# 07_-_Leds_-_OptoCoupler_Input.net
KiCad netlist of a schematic drawn in Altium Designer
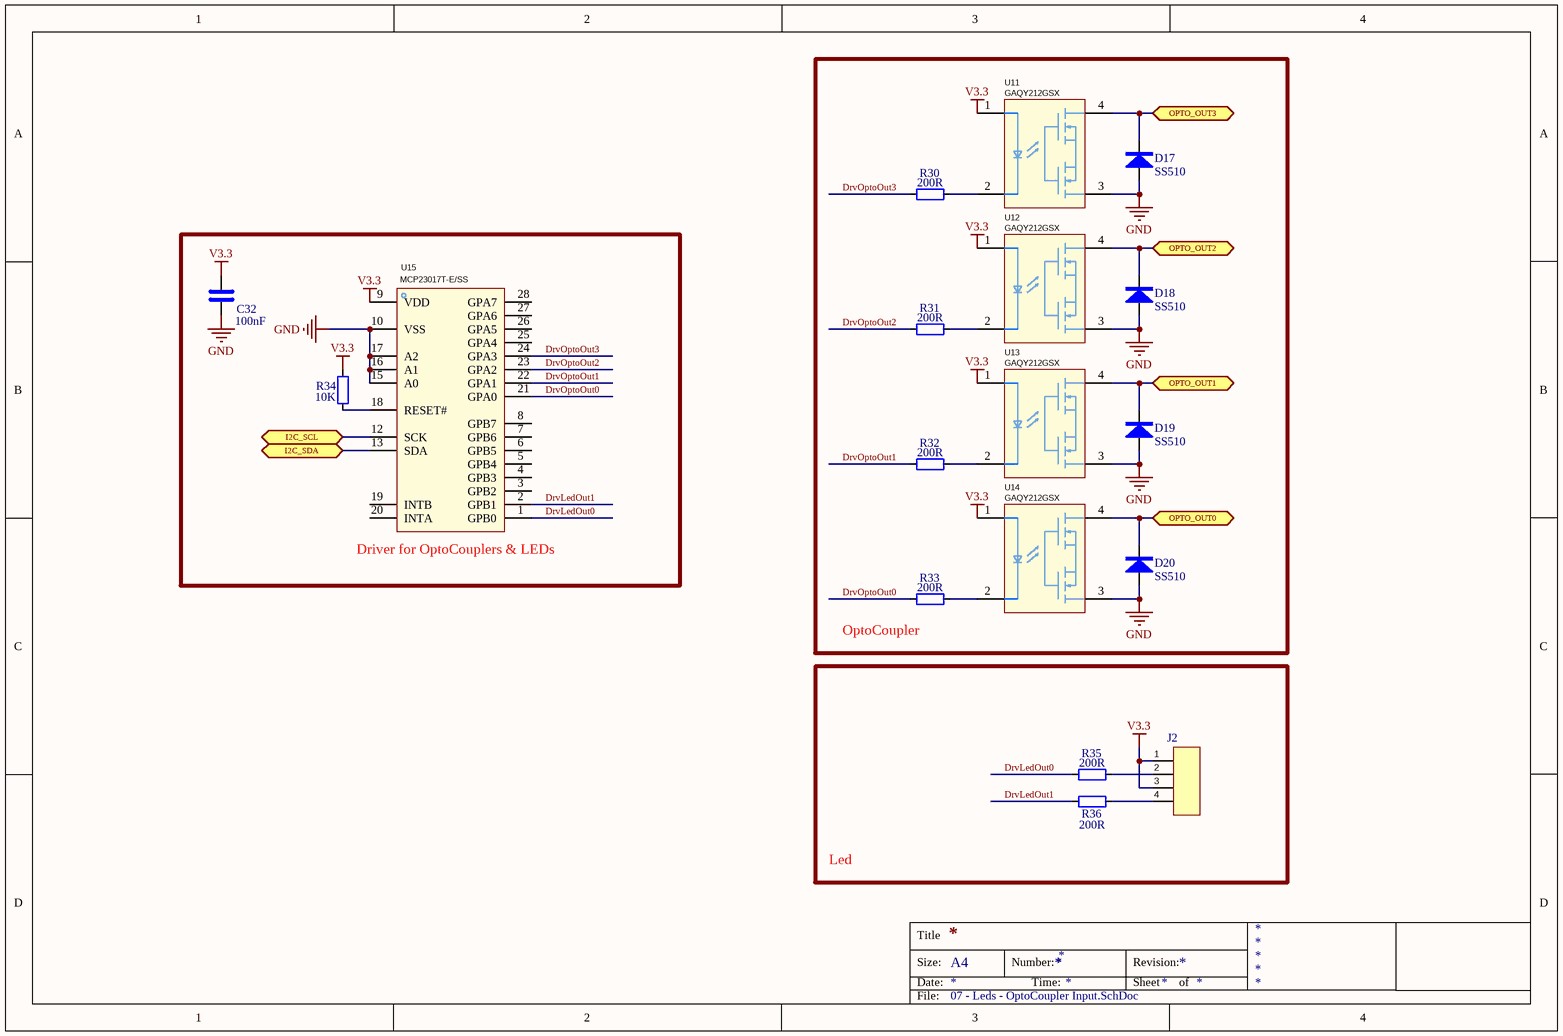
[diagram p0: 07 - Leds - OptoCoupler Input.SchDoc]

(export (version "E")
  (design (tool "Eeschema 10.0.6"))
  (components
    (comp (ref "C32")
      (value "100nF")
      (footprint "CAP_0603")
      (fields (field (name "LCSC PART") "C6119867"))
      (libsource (lib "WalterFeels") (part "C"))
    )
    (comp (ref "D17")
      (value "SS510")
      (footprint "S1M-13-F")
      (fields (field (name "LCSC PART") "C65010") (field (name "Comment") "DIODE SCHOTTKY 100V 5A DO214AC"))
      (libsource (lib "MIKRODEV_LIBRARY_v2") (part "DIODE SCHOTTKY 100V 5A DO214AC"))
    )
    (comp (ref "D18")
      (value "SS510")
      (footprint "S1M-13-F")
      (fields (field (name "LCSC PART") "C65010") (field (name "Comment") "DIODE SCHOTTKY 100V 5A DO214AC"))
      (libsource (lib "MIKRODEV_LIBRARY_v2") (part "DIODE SCHOTTKY 100V 5A DO214AC"))
    )
    (comp (ref "D19")
      (value "SS510")
      (footprint "S1M-13-F")
      (fields (field (name "LCSC PART") "C65010") (field (name "Comment") "DIODE SCHOTTKY 100V 5A DO214AC"))
      (libsource (lib "MIKRODEV_LIBRARY_v2") (part "DIODE SCHOTTKY 100V 5A DO214AC"))
    )
    (comp (ref "D20")
      (value "SS510")
      (footprint "S1M-13-F")
      (fields (field (name "LCSC PART") "C65010") (field (name "Comment") "DIODE SCHOTTKY 100V 5A DO214AC"))
      (libsource (lib "MIKRODEV_LIBRARY_v2") (part "DIODE SCHOTTKY 100V 5A DO214AC"))
    )
    (comp (ref "J2")
      (value "Conn_01x04_Male")
      (footprint "PinHeader_1x04_P2.54mm_Vertical")
      (description "4P 2.54mm Single Row 1x4P Plugin,P=2.54mm Pin Headers ROHS")
      (fields (field (name "LCSC PART") "C5116483"))
      (libsource (lib "WalterFeels") (part "Conn_01x04_Male"))
    )
    (comp (ref "R30")
      (value "200R")
      (footprint "RES_0603")
      (fields (field (name "LCSC PART") "C2907123") (field (name "Comment") "200R %5"))
      (libsource (lib "Device") (part "R"))
    )
    (comp (ref "R31")
      (value "200R")
      (footprint "RES_0603")
      (fields (field (name "LCSC PART") "C2907123") (field (name "Comment") "200R %5"))
      (libsource (lib "Device") (part "R"))
    )
    (comp (ref "R32")
      (value "200R")
      (footprint "RES_0603")
      (fields (field (name "LCSC PART") "C2907123") (field (name "Comment") "200R %5"))
      (libsource (lib "Device") (part "R"))
    )
    (comp (ref "R33")
      (value "200R")
      (footprint "RES_0603")
      (fields (field (name "LCSC PART") "C2907123") (field (name "Comment") "200R %5"))
      (libsource (lib "Device") (part "R"))
    )
    (comp (ref "R34")
      (value "10K")
      (footprint "RES_0603")
      (fields (field (name "LCSC PART") "C25804") (field (name "Comment") "10K 1%"))
      (libsource (lib "") (part "R_1"))
    )
    (comp (ref "R35")
      (value "200R")
      (footprint "RES_0603")
      (fields (field (name "LCSC PART") "C2907123") (field (name "Comment") "200R %5"))
      (libsource (lib "Device") (part "R"))
    )
    (comp (ref "R36")
      (value "200R")
      (footprint "RES_0603")
      (fields (field (name "LCSC PART") "C2907123") (field (name "Comment") "200R %5"))
      (libsource (lib "Device") (part "R"))
    )
    (comp (ref "U11")
      (value "GAQY212GSX")
      (footprint "SOP-4_L4.3-W4.4-P2.54-LS6.8-TR")
      (description "1.32V 60V 180mΩ 1A SOP-4 Solid State Relays (MOS Output) ROHS")
      (fields (field (name "MANUFACTURER") "SUPSiC(国晶微半导体)") (field (name "LCSC PART") "C19271988"))
      (libsource (lib "WalterFeels") (part "GAQY212GSX"))
    )
    (comp (ref "U12")
      (value "GAQY212GSX")
      (footprint "SOP-4_L4.3-W4.4-P2.54-LS6.8-TR")
      (description "1.32V 60V 180mΩ 1A SOP-4 Solid State Relays (MOS Output) ROHS")
      (fields (field (name "MANUFACTURER") "SUPSiC(国晶微半导体)") (field (name "LCSC PART") "C19271988"))
      (libsource (lib "WalterFeels") (part "GAQY212GSX"))
    )
    (comp (ref "U13")
      (value "GAQY212GSX")
      (footprint "SOP-4_L4.3-W4.4-P2.54-LS6.8-TR")
      (description "1.32V 60V 180mΩ 1A SOP-4 Solid State Relays (MOS Output) ROHS")
      (fields (field (name "MANUFACTURER") "SUPSiC(国晶微半导体)") (field (name "LCSC PART") "C19271988"))
      (libsource (lib "WalterFeels") (part "GAQY212GSX"))
    )
    (comp (ref "U14")
      (value "GAQY212GSX")
      (footprint "SOP-4_L4.3-W4.4-P2.54-LS6.8-TR")
      (description "1.32V 60V 180mΩ 1A SOP-4 Solid State Relays (MOS Output) ROHS")
      (fields (field (name "MANUFACTURER") "SUPSiC(国晶微半导体)") (field (name "LCSC PART") "C19271988"))
      (libsource (lib "WalterFeels") (part "GAQY212GSX"))
    )
    (comp (ref "U15")
      (value "MCP23017T-E/SS")
      (footprint "SSOP-28_L10.2-W5.3-P0.65-LS7.8-BL")
      (description "16-Bit I/O Expander with Serial Interface")
      (fields (field (name "MANUFACTURER") "MICROCHIP(美国微芯)") (field (name "LCSC PART") "C558584"))
      (libsource (lib "WalterFeels") (part "MCP23017T-E/SS"))
    )
  )
  (nets
    (net (code "1") (name "/DrvLedOut0") (class "Default")
      (node (ref "R35") (pin "1") (pinfunction "1_1") (pintype "passive"))
      (node (ref "U15") (pin "1") (pinfunction "GPB0_1") (pintype "passive"))
    )
    (net (code "2") (name "/DrvLedOut1") (class "Default")
      (node (ref "R36") (pin "1") (pinfunction "1_1") (pintype "passive"))
      (node (ref "U15") (pin "2") (pinfunction "GPB1_2") (pintype "passive"))
    )
    (net (code "3") (name "/DrvOptoOut0") (class "Default")
      (node (ref "R33") (pin "1") (pinfunction "1_1") (pintype "passive"))
      (node (ref "U15") (pin "21") (pinfunction "GPA0_21") (pintype "passive"))
    )
    (net (code "4") (name "/DrvOptoOut1") (class "Default")
      (node (ref "R32") (pin "1") (pinfunction "1_1") (pintype "passive"))
      (node (ref "U15") (pin "22") (pinfunction "GPA1_22") (pintype "passive"))
    )
    (net (code "5") (name "/DrvOptoOut2") (class "Default")
      (node (ref "R31") (pin "1") (pinfunction "1_1") (pintype "passive"))
      (node (ref "U15") (pin "23") (pinfunction "GPA2_23") (pintype "passive"))
    )
    (net (code "6") (name "/DrvOptoOut3") (class "Default")
      (node (ref "R30") (pin "1") (pinfunction "1_1") (pintype "passive"))
      (node (ref "U15") (pin "24") (pinfunction "GPA3_24") (pintype "passive"))
    )
    (net (code "7") (name "/I2C_SCL") (class "Default")
      (node (ref "U15") (pin "12") (pinfunction "SCK_12") (pintype "passive"))
    )
    (net (code "8") (name "/I2C_SDA") (class "Default")
      (node (ref "U15") (pin "13") (pinfunction "SDA_13") (pintype "passive"))
    )
    (net (code "9") (name "/OPTO_OUT0") (class "Default")
      (node (ref "D20") (pin "1") (pinfunction "K_1") (pintype "passive"))
      (node (ref "U14") (pin "4") (pinfunction "4_4") (pintype "passive"))
    )
    (net (code "10") (name "/OPTO_OUT1") (class "Default")
      (node (ref "D19") (pin "1") (pinfunction "K_1") (pintype "passive"))
      (node (ref "U13") (pin "4") (pinfunction "4_4") (pintype "passive"))
    )
    (net (code "11") (name "/OPTO_OUT2") (class "Default")
      (node (ref "D18") (pin "1") (pinfunction "K_1") (pintype "passive"))
      (node (ref "U12") (pin "4") (pinfunction "4_4") (pintype "passive"))
    )
    (net (code "12") (name "/OPTO_OUT3") (class "Default")
      (node (ref "D17") (pin "1") (pinfunction "K_1") (pintype "passive"))
      (node (ref "U11") (pin "4") (pinfunction "4_4") (pintype "passive"))
    )
    (net (code "13") (name "GND") (class "Default")
      (node (ref "C32") (pin "2") (pinfunction "2_2") (pintype "passive"))
      (node (ref "D17") (pin "2") (pinfunction "A_2") (pintype "passive"))
      (node (ref "D18") (pin "2") (pinfunction "A_2") (pintype "passive"))
      (node (ref "D19") (pin "2") (pinfunction "A_2") (pintype "passive"))
      (node (ref "D20") (pin "2") (pinfunction "A_2") (pintype "passive"))
      (node (ref "U11") (pin "3") (pinfunction "3_3") (pintype "passive"))
      (node (ref "U12") (pin "3") (pinfunction "3_3") (pintype "passive"))
      (node (ref "U13") (pin "3") (pinfunction "3_3") (pintype "passive"))
      (node (ref "U14") (pin "3") (pinfunction "3_3") (pintype "passive"))
      (node (ref "U15") (pin "10") (pinfunction "VSS_10") (pintype "passive"))
      (node (ref "U15") (pin "15") (pinfunction "A0_15") (pintype "passive"))
      (node (ref "U15") (pin "16") (pinfunction "A1_16") (pintype "passive"))
      (node (ref "U15") (pin "17") (pinfunction "A2_17") (pintype "passive"))
    )
    (net (code "14") (name "Net-(J2-Pin_2)") (class "Default")
      (node (ref "J2") (pin "2") (pinfunction "Pin_2_2") (pintype "passive"))
      (node (ref "R35") (pin "2") (pinfunction "2_2") (pintype "passive"))
    )
    (net (code "15") (name "Net-(J2-Pin_4)") (class "Default")
      (node (ref "J2") (pin "4") (pinfunction "Pin_4_4") (pintype "passive"))
      (node (ref "R36") (pin "2") (pinfunction "2_2") (pintype "passive"))
    )
    (net (code "16") (name "Net-(R30-Pad2)") (class "Default")
      (node (ref "R30") (pin "2") (pinfunction "2_2") (pintype "passive"))
      (node (ref "U11") (pin "2") (pinfunction "2_2") (pintype "passive"))
    )
    (net (code "17") (name "Net-(R31-Pad2)") (class "Default")
      (node (ref "R31") (pin "2") (pinfunction "2_2") (pintype "passive"))
      (node (ref "U12") (pin "2") (pinfunction "2_2") (pintype "passive"))
    )
    (net (code "18") (name "Net-(R32-Pad2)") (class "Default")
      (node (ref "R32") (pin "2") (pinfunction "2_2") (pintype "passive"))
      (node (ref "U13") (pin "2") (pinfunction "2_2") (pintype "passive"))
    )
    (net (code "19") (name "Net-(R33-Pad2)") (class "Default")
      (node (ref "R33") (pin "2") (pinfunction "2_2") (pintype "passive"))
      (node (ref "U14") (pin "2") (pinfunction "2_2") (pintype "passive"))
    )
    (net (code "20") (name "Net-(U15-RESET#)") (class "Default")
      (node (ref "R34") (pin "1") (pinfunction "1_1") (pintype "passive"))
      (node (ref "U15") (pin "18") (pinfunction "RESET#_18") (pintype "passive"))
    )
    (net (code "21") (name "V3.3") (class "Default")
      (node (ref "C32") (pin "1") (pinfunction "1_1") (pintype "passive"))
      (node (ref "J2") (pin "1") (pinfunction "Pin_1_1") (pintype "passive"))
      (node (ref "J2") (pin "3") (pinfunction "Pin_3_3") (pintype "passive"))
      (node (ref "R34") (pin "2") (pinfunction "2_2") (pintype "passive"))
      (node (ref "U11") (pin "1") (pinfunction "1_1") (pintype "passive"))
      (node (ref "U12") (pin "1") (pinfunction "1_1") (pintype "passive"))
      (node (ref "U13") (pin "1") (pinfunction "1_1") (pintype "passive"))
      (node (ref "U14") (pin "1") (pinfunction "1_1") (pintype "passive"))
      (node (ref "U15") (pin "9") (pinfunction "VDD_9") (pintype "passive"))
    )
    (net (code "22") (name "unconnected-(U15-GPA4-Pad25)") (class "Default")
      (node (ref "U15") (pin "25") (pinfunction "GPA4_25") (pintype "passive"))
    )
    (net (code "23") (name "unconnected-(U15-GPA5-Pad26)") (class "Default")
      (node (ref "U15") (pin "26") (pinfunction "GPA5_26") (pintype "passive"))
    )
    (net (code "24") (name "unconnected-(U15-GPA6-Pad27)") (class "Default")
      (node (ref "U15") (pin "27") (pinfunction "GPA6_27") (pintype "passive"))
    )
    (net (code "25") (name "unconnected-(U15-GPA7-Pad28)") (class "Default")
      (node (ref "U15") (pin "28") (pinfunction "GPA7_28") (pintype "passive"))
    )
    (net (code "26") (name "unconnected-(U15-GPB2-Pad3)") (class "Default")
      (node (ref "U15") (pin "3") (pinfunction "GPB2_3") (pintype "passive"))
    )
    (net (code "27") (name "unconnected-(U15-GPB3-Pad4)") (class "Default")
      (node (ref "U15") (pin "4") (pinfunction "GPB3_4") (pintype "passive"))
    )
    (net (code "28") (name "unconnected-(U15-GPB4-Pad5)") (class "Default")
      (node (ref "U15") (pin "5") (pinfunction "GPB4_5") (pintype "passive"))
    )
    (net (code "29") (name "unconnected-(U15-GPB5-Pad6)") (class "Default")
      (node (ref "U15") (pin "6") (pinfunction "GPB5_6") (pintype "passive"))
    )
    (net (code "30") (name "unconnected-(U15-GPB6-Pad7)") (class "Default")
      (node (ref "U15") (pin "7") (pinfunction "GPB6_7") (pintype "passive"))
    )
    (net (code "31") (name "unconnected-(U15-GPB7-Pad8)") (class "Default")
      (node (ref "U15") (pin "8") (pinfunction "GPB7_8") (pintype "passive"))
    )
    (net (code "32") (name "unconnected-(U15-INTA-Pad20)") (class "Default")
      (node (ref "U15") (pin "20") (pinfunction "INTA_20") (pintype "passive"))
    )
    (net (code "33") (name "unconnected-(U15-INTB-Pad19)") (class "Default")
      (node (ref "U15") (pin "19") (pinfunction "INTB_19") (pintype "passive"))
    )
    (net (code "34") (name "unconnected-(U15-NC-Pad11)") (class "Default")
      (node (ref "U15") (pin "11") (pinfunction "NC_11") (pintype "passive"))
    )
    (net (code "35") (name "unconnected-(U15-NC-Pad14)") (class "Default")
      (node (ref "U15") (pin "14") (pinfunction "NC_14") (pintype "passive"))
    )
  )
)
